# THS788_1.net
KiCad netlist of a schematic drawn in Altium Designer
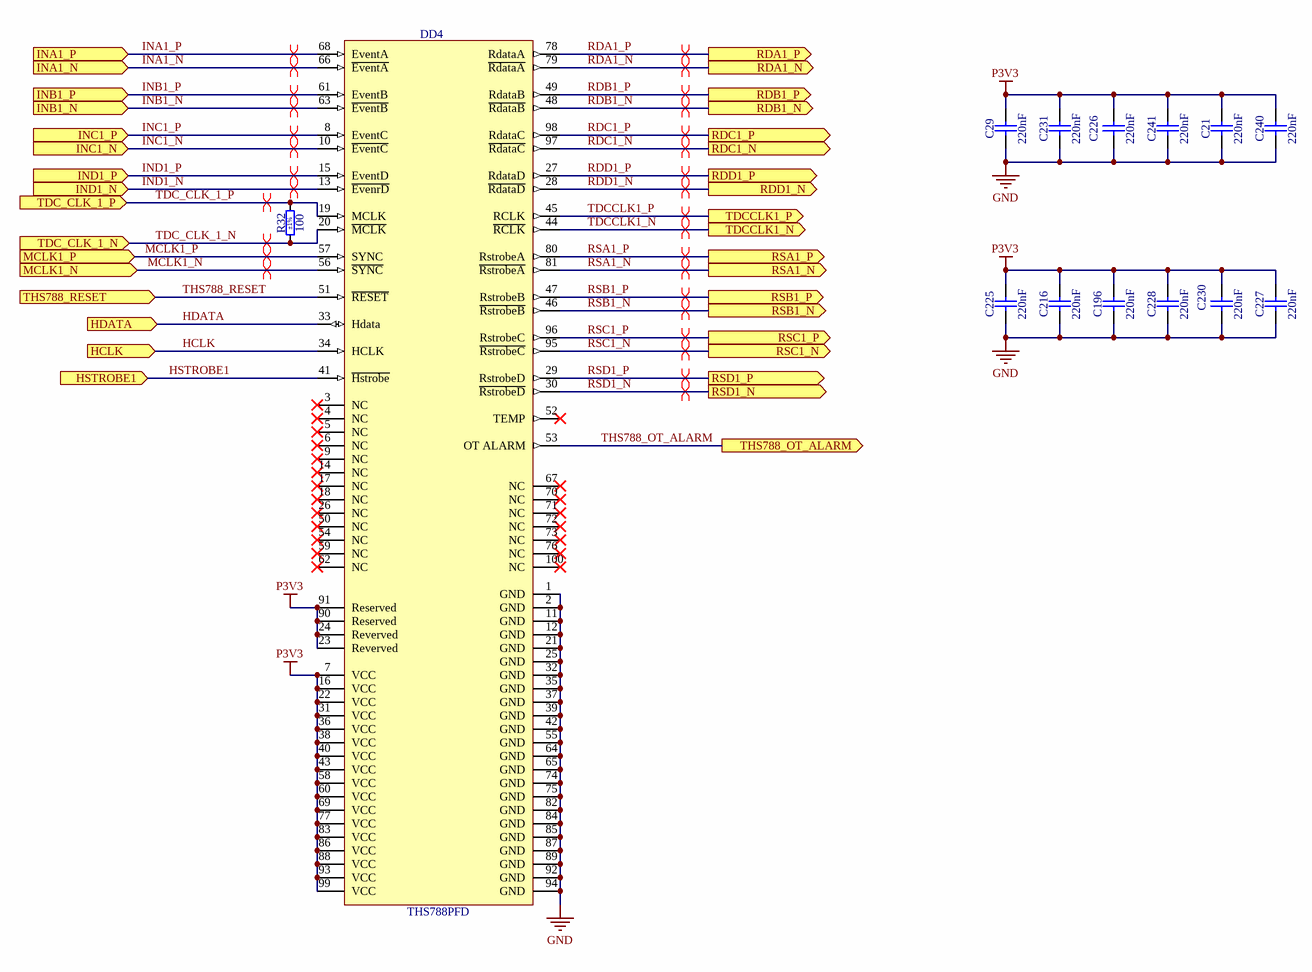
[diagram p0: THS788_1.SchDoc]

(export (version "E")
  (design (tool "Eeschema 10.0.6"))
  (components
    (comp (ref "C21")
      (value "220nF")
      (footprint "CAPC2012X135N")
      (description "Non-polarised capacitor")
      (fields
        (field (name "PART NUMBER") "CC0805_220NF_50V_10%_X7R")
        (field (name "VOLTAGE") "50V")
        (field (name "AUTHOR") "CERN DEM JLC")
      )
      (libsource (lib "Capacitors") (part "Capacitor - non polarized"))
    )
    (comp (ref "C29")
      (value "220nF")
      (footprint "CAPC2012X135N")
      (description "Non-polarised capacitor")
      (fields
        (field (name "PART NUMBER") "CC0805_220NF_50V_10%_X7R")
        (field (name "VOLTAGE") "50V")
        (field (name "AUTHOR") "CERN DEM JLC")
      )
      (libsource (lib "Capacitors") (part "Capacitor - non polarized"))
    )
    (comp (ref "C196")
      (value "220nF")
      (footprint "CAPC2012X135N")
      (description "Non-polarised capacitor")
      (fields
        (field (name "PART NUMBER") "CC0805_220NF_50V_10%_X7R")
        (field (name "VOLTAGE") "50V")
        (field (name "AUTHOR") "CERN DEM JLC")
      )
      (libsource (lib "Capacitors") (part "Capacitor - non polarized"))
    )
    (comp (ref "C216")
      (value "220nF")
      (footprint "CAPC2012X135N")
      (description "Non-polarised capacitor")
      (fields
        (field (name "PART NUMBER") "CC0805_220NF_50V_10%_X7R")
        (field (name "VOLTAGE") "50V")
        (field (name "AUTHOR") "CERN DEM JLC")
      )
      (libsource (lib "Capacitors") (part "Capacitor - non polarized"))
    )
    (comp (ref "C225")
      (value "220nF")
      (footprint "CAPC2012X135N")
      (description "Non-polarised capacitor")
      (fields
        (field (name "PART NUMBER") "CC0805_220NF_50V_10%_X7R")
        (field (name "VOLTAGE") "50V")
        (field (name "AUTHOR") "CERN DEM JLC")
      )
      (libsource (lib "Capacitors") (part "Capacitor - non polarized"))
    )
    (comp (ref "C226")
      (value "220nF")
      (footprint "CAPC2012X135N")
      (description "Non-polarised capacitor")
      (fields
        (field (name "PART NUMBER") "CC0805_220NF_50V_10%_X7R")
        (field (name "VOLTAGE") "50V")
        (field (name "AUTHOR") "CERN DEM JLC")
      )
      (libsource (lib "Capacitors") (part "Capacitor - non polarized"))
    )
    (comp (ref "C227")
      (value "220nF")
      (footprint "CAPC2012X135N")
      (description "Non-polarised capacitor")
      (fields
        (field (name "PART NUMBER") "CC0805_220NF_50V_10%_X7R")
        (field (name "VOLTAGE") "50V")
        (field (name "AUTHOR") "CERN DEM JLC")
      )
      (libsource (lib "Capacitors") (part "Capacitor - non polarized"))
    )
    (comp (ref "C228")
      (value "220nF")
      (footprint "CAPC2012X135N")
      (description "Non-polarised capacitor")
      (fields
        (field (name "PART NUMBER") "CC0805_220NF_50V_10%_X7R")
        (field (name "VOLTAGE") "50V")
        (field (name "AUTHOR") "CERN DEM JLC")
      )
      (libsource (lib "Capacitors") (part "Capacitor - non polarized"))
    )
    (comp (ref "C230")
      (value "220nF")
      (footprint "CAPC2012X135N")
      (description "Non-polarised capacitor")
      (fields
        (field (name "PART NUMBER") "CC0805_220NF_50V_10%_X7R")
        (field (name "VOLTAGE") "50V")
        (field (name "AUTHOR") "CERN DEM JLC")
      )
      (libsource (lib "Capacitors") (part "Capacitor - non polarized"))
    )
    (comp (ref "C231")
      (value "220nF")
      (footprint "CAPC2012X135N")
      (description "Non-polarised capacitor")
      (fields
        (field (name "PART NUMBER") "CC0805_220NF_50V_10%_X7R")
        (field (name "VOLTAGE") "50V")
        (field (name "AUTHOR") "CERN DEM JLC")
      )
      (libsource (lib "Capacitors") (part "Capacitor - non polarized"))
    )
    (comp (ref "C240")
      (value "220nF")
      (footprint "CAPC2012X135N")
      (description "Non-polarised capacitor")
      (fields
        (field (name "PART NUMBER") "CC0805_220NF_50V_10%_X7R")
        (field (name "VOLTAGE") "50V")
        (field (name "AUTHOR") "CERN DEM JLC")
      )
      (libsource (lib "Capacitors") (part "Capacitor - non polarized"))
    )
    (comp (ref "C241")
      (value "220nF")
      (footprint "CAPC2012X135N")
      (description "Non-polarised capacitor")
      (fields
        (field (name "PART NUMBER") "CC0805_220NF_50V_10%_X7R")
        (field (name "VOLTAGE") "50V")
        (field (name "AUTHOR") "CERN DEM JLC")
      )
      (libsource (lib "Capacitors") (part "Capacitor - non polarized"))
    )
    (comp (ref "DD4")
      (value "THS788PFD")
      (footprint "TEXAS_PFD (S-PQFP-G100)")
      (description "Quad-Channel Time Measurement Unit (TMU)")
      (fields (field (name "MANUFACTURER") "TEXAS INSTRUMENTS") (field (name "AUTHOR") "CERN DEM HF"))
      (libsource (lib "ICs And Semiconductors") (part "THS788PFD"))
    )
    (comp (ref "R32")
      (value "100")
      (footprint "RESC1608X55N")
      (description "Resistor - 1%")
      (fields
        (field (name "TOLERANCE") "±1%")
        (field (name "PART NUMBER") "R0603_100R_1%_0.1W_100PPM")
        (field (name "POWER") "0.1W")
        (field (name "AUTHOR") "CERN DEM JLC")
      )
      (libsource (lib "Resistors") (part "Resistor - 1%"))
    )
  )
  (nets
    (net (code "1") (name "/HCLK") (class "Default")
      (node (ref "DD4") (pin "34") (pinfunction "HCLK_34") (pintype "input"))
    )
    (net (code "2") (name "/HDATA") (class "Default")
      (node (ref "DD4") (pin "33") (pinfunction "Hdata_33") (pintype "bidirectional"))
    )
    (net (code "3") (name "/HSTROBE1") (class "Default")
      (node (ref "DD4") (pin "41") (pinfunction "~{Hstrobe}_41") (pintype "input"))
    )
    (net (code "4") (name "/INA1_N") (class "Default")
      (node (ref "DD4") (pin "66") (pinfunction "~{EventA}_66") (pintype "input"))
    )
    (net (code "5") (name "/INA1_P") (class "Default")
      (node (ref "DD4") (pin "68") (pinfunction "EventA_68") (pintype "input"))
    )
    (net (code "6") (name "/INB1_N") (class "Default")
      (node (ref "DD4") (pin "63") (pinfunction "~{EventB}_63") (pintype "input"))
    )
    (net (code "7") (name "/INB1_P") (class "Default")
      (node (ref "DD4") (pin "61") (pinfunction "EventB_61") (pintype "input"))
    )
    (net (code "8") (name "/INC1_N") (class "Default")
      (node (ref "DD4") (pin "10") (pinfunction "~{EventC}_10") (pintype "input"))
    )
    (net (code "9") (name "/INC1_P") (class "Default")
      (node (ref "DD4") (pin "8") (pinfunction "EventC_8") (pintype "input"))
    )
    (net (code "10") (name "/IND1_N") (class "Default")
      (node (ref "DD4") (pin "13") (pinfunction "~{EvenrD}_13") (pintype "input"))
    )
    (net (code "11") (name "/IND1_P") (class "Default")
      (node (ref "DD4") (pin "15") (pinfunction "EventD_15") (pintype "input"))
    )
    (net (code "12") (name "/MCLK1_N") (class "Default")
      (node (ref "DD4") (pin "56") (pinfunction "~{SYNC}_56") (pintype "input"))
    )
    (net (code "13") (name "/MCLK1_P") (class "Default")
      (node (ref "DD4") (pin "57") (pinfunction "SYNC_57") (pintype "input"))
    )
    (net (code "14") (name "/RDA1_N") (class "Default")
      (node (ref "DD4") (pin "79") (pinfunction "~{RdataA}_79") (pintype "output"))
    )
    (net (code "15") (name "/RDA1_P") (class "Default")
      (node (ref "DD4") (pin "78") (pinfunction "RdataA_78") (pintype "output"))
    )
    (net (code "16") (name "/RDB1_N") (class "Default")
      (node (ref "DD4") (pin "48") (pinfunction "~{RdataB}_48") (pintype "output"))
    )
    (net (code "17") (name "/RDB1_P") (class "Default")
      (node (ref "DD4") (pin "49") (pinfunction "RdataB_49") (pintype "output"))
    )
    (net (code "18") (name "/RDC1_N") (class "Default")
      (node (ref "DD4") (pin "97") (pinfunction "~{RdataC}_97") (pintype "output"))
    )
    (net (code "19") (name "/RDC1_P") (class "Default")
      (node (ref "DD4") (pin "98") (pinfunction "RdataC_98") (pintype "output"))
    )
    (net (code "20") (name "/RDD1_N") (class "Default")
      (node (ref "DD4") (pin "28") (pinfunction "~{RdataD}_28") (pintype "output"))
    )
    (net (code "21") (name "/RDD1_P") (class "Default")
      (node (ref "DD4") (pin "27") (pinfunction "RdataD_27") (pintype "output"))
    )
    (net (code "22") (name "/RSA1_N") (class "Default")
      (node (ref "DD4") (pin "81") (pinfunction "~{RstrobeA}_81") (pintype "output"))
    )
    (net (code "23") (name "/RSA1_P") (class "Default")
      (node (ref "DD4") (pin "80") (pinfunction "RstrobeA_80") (pintype "output"))
    )
    (net (code "24") (name "/RSB1_N") (class "Default")
      (node (ref "DD4") (pin "46") (pinfunction "~{RstrobeB}_46") (pintype "output"))
    )
    (net (code "25") (name "/RSB1_P") (class "Default")
      (node (ref "DD4") (pin "47") (pinfunction "RstrobeB_47") (pintype "output"))
    )
    (net (code "26") (name "/RSC1_N") (class "Default")
      (node (ref "DD4") (pin "95") (pinfunction "~{RstrobeC}_95") (pintype "output"))
    )
    (net (code "27") (name "/RSC1_P") (class "Default")
      (node (ref "DD4") (pin "96") (pinfunction "RstrobeC_96") (pintype "output"))
    )
    (net (code "28") (name "/RSD1_N") (class "Default")
      (node (ref "DD4") (pin "30") (pinfunction "~{RstrobeD}_30") (pintype "output"))
    )
    (net (code "29") (name "/RSD1_P") (class "Default")
      (node (ref "DD4") (pin "29") (pinfunction "RstrobeD_29") (pintype "output"))
    )
    (net (code "30") (name "/TDCCLK1_N") (class "Default")
      (node (ref "DD4") (pin "44") (pinfunction "~{RCLK}_44") (pintype "output"))
    )
    (net (code "31") (name "/TDCCLK1_P") (class "Default")
      (node (ref "DD4") (pin "45") (pinfunction "RCLK_45") (pintype "output"))
    )
    (net (code "32") (name "/TDC_CLK_1_N") (class "Default")
      (node (ref "DD4") (pin "20") (pinfunction "~{MCLK}_20") (pintype "input"))
      (node (ref "R32") (pin "1") (pinfunction "1_1") (pintype "passive"))
    )
    (net (code "33") (name "/TDC_CLK_1_P") (class "Default")
      (node (ref "DD4") (pin "19") (pinfunction "MCLK_19") (pintype "input"))
      (node (ref "R32") (pin "2") (pinfunction "2_2") (pintype "passive"))
    )
    (net (code "34") (name "/THS788_OT_ALARM") (class "Default")
      (node (ref "DD4") (pin "53") (pinfunction "OT_ALARM_53") (pintype "output"))
    )
    (net (code "35") (name "/THS788_RESET") (class "Default")
      (node (ref "DD4") (pin "51") (pinfunction "~{RESET}_51") (pintype "input"))
    )
    (net (code "36") (name "GND") (class "Default")
      (node (ref "C196") (pin "1") (pinfunction "1_1") (pintype "passive"))
      (node (ref "C21") (pin "1") (pinfunction "1_1") (pintype "passive"))
      (node (ref "C216") (pin "1") (pinfunction "1_1") (pintype "passive"))
      (node (ref "C225") (pin "1") (pinfunction "1_1") (pintype "passive"))
      (node (ref "C226") (pin "1") (pinfunction "1_1") (pintype "passive"))
      (node (ref "C227") (pin "1") (pinfunction "1_1") (pintype "passive"))
      (node (ref "C228") (pin "1") (pinfunction "1_1") (pintype "passive"))
      (node (ref "C230") (pin "1") (pinfunction "1_1") (pintype "passive"))
      (node (ref "C231") (pin "1") (pinfunction "1_1") (pintype "passive"))
      (node (ref "C240") (pin "1") (pinfunction "1_1") (pintype "passive"))
      (node (ref "C241") (pin "1") (pinfunction "1_1") (pintype "passive"))
      (node (ref "C29") (pin "1") (pinfunction "1_1") (pintype "passive"))
      (node (ref "DD4") (pin "1") (pinfunction "GND_1") (pintype "power_in"))
      (node (ref "DD4") (pin "11") (pinfunction "GND_11") (pintype "power_in"))
      (node (ref "DD4") (pin "12") (pinfunction "GND_12") (pintype "power_in"))
      (node (ref "DD4") (pin "2") (pinfunction "GND_2") (pintype "power_in"))
      (node (ref "DD4") (pin "21") (pinfunction "GND_21") (pintype "power_in"))
      (node (ref "DD4") (pin "25") (pinfunction "GND_25") (pintype "power_in"))
      (node (ref "DD4") (pin "32") (pinfunction "GND_32") (pintype "power_in"))
      (node (ref "DD4") (pin "35") (pinfunction "GND_35") (pintype "power_in"))
      (node (ref "DD4") (pin "37") (pinfunction "GND_37") (pintype "power_in"))
      (node (ref "DD4") (pin "39") (pinfunction "GND_39") (pintype "power_in"))
      (node (ref "DD4") (pin "42") (pinfunction "GND_42") (pintype "power_in"))
      (node (ref "DD4") (pin "55") (pinfunction "GND_55") (pintype "power_in"))
      (node (ref "DD4") (pin "64") (pinfunction "GND_64") (pintype "power_in"))
      (node (ref "DD4") (pin "65") (pinfunction "GND_65") (pintype "power_in"))
      (node (ref "DD4") (pin "74") (pinfunction "GND_74") (pintype "power_in"))
      (node (ref "DD4") (pin "75") (pinfunction "GND_75") (pintype "power_in"))
      (node (ref "DD4") (pin "82") (pinfunction "GND_82") (pintype "power_in"))
      (node (ref "DD4") (pin "84") (pinfunction "GND_84") (pintype "power_in"))
      (node (ref "DD4") (pin "85") (pinfunction "GND_85") (pintype "power_in"))
      (node (ref "DD4") (pin "87") (pinfunction "GND_87") (pintype "power_in"))
      (node (ref "DD4") (pin "89") (pinfunction "GND_89") (pintype "power_in"))
      (node (ref "DD4") (pin "92") (pinfunction "GND_92") (pintype "power_in"))
      (node (ref "DD4") (pin "94") (pinfunction "GND_94") (pintype "power_in"))
    )
    (net (code "37") (name "P3V3") (class "Default")
      (node (ref "C196") (pin "2") (pinfunction "2_2") (pintype "passive"))
      (node (ref "C21") (pin "2") (pinfunction "2_2") (pintype "passive"))
      (node (ref "C216") (pin "2") (pinfunction "2_2") (pintype "passive"))
      (node (ref "C225") (pin "2") (pinfunction "2_2") (pintype "passive"))
      (node (ref "C226") (pin "2") (pinfunction "2_2") (pintype "passive"))
      (node (ref "C227") (pin "2") (pinfunction "2_2") (pintype "passive"))
      (node (ref "C228") (pin "2") (pinfunction "2_2") (pintype "passive"))
      (node (ref "C230") (pin "2") (pinfunction "2_2") (pintype "passive"))
      (node (ref "C231") (pin "2") (pinfunction "2_2") (pintype "passive"))
      (node (ref "C240") (pin "2") (pinfunction "2_2") (pintype "passive"))
      (node (ref "C241") (pin "2") (pinfunction "2_2") (pintype "passive"))
      (node (ref "C29") (pin "2") (pinfunction "2_2") (pintype "passive"))
      (node (ref "DD4") (pin "16") (pinfunction "VCC_16") (pintype "power_in"))
      (node (ref "DD4") (pin "22") (pinfunction "VCC_22") (pintype "power_in"))
      (node (ref "DD4") (pin "23") (pinfunction "Reverved_23") (pintype "passive"))
      (node (ref "DD4") (pin "24") (pinfunction "Reverved_24") (pintype "passive"))
      (node (ref "DD4") (pin "31") (pinfunction "VCC_31") (pintype "power_in"))
      (node (ref "DD4") (pin "36") (pinfunction "VCC_36") (pintype "power_in"))
      (node (ref "DD4") (pin "38") (pinfunction "VCC_38") (pintype "power_in"))
      (node (ref "DD4") (pin "40") (pinfunction "VCC_40") (pintype "power_in"))
      (node (ref "DD4") (pin "43") (pinfunction "VCC_43") (pintype "power_in"))
      (node (ref "DD4") (pin "58") (pinfunction "VCC_58") (pintype "power_in"))
      (node (ref "DD4") (pin "60") (pinfunction "VCC_60") (pintype "power_in"))
      (node (ref "DD4") (pin "69") (pinfunction "VCC_69") (pintype "power_in"))
      (node (ref "DD4") (pin "7") (pinfunction "VCC_7") (pintype "power_in"))
      (node (ref "DD4") (pin "77") (pinfunction "VCC_77") (pintype "power_in"))
      (node (ref "DD4") (pin "83") (pinfunction "VCC_83") (pintype "power_in"))
      (node (ref "DD4") (pin "86") (pinfunction "VCC_86") (pintype "power_in"))
      (node (ref "DD4") (pin "88") (pinfunction "VCC_88") (pintype "power_in"))
      (node (ref "DD4") (pin "90") (pinfunction "Reserved_90") (pintype "passive"))
      (node (ref "DD4") (pin "91") (pinfunction "Reserved_91") (pintype "passive"))
      (node (ref "DD4") (pin "93") (pinfunction "VCC_93") (pintype "power_in"))
      (node (ref "DD4") (pin "99") (pinfunction "VCC_99") (pintype "power_in"))
    )
    (net (code "38") (name "unconnected-(DD4-NC-Pad3)") (class "Default")
      (node (ref "DD4") (pin "3") (pinfunction "NC_3") (pintype "passive+no_connect"))
    )
    (net (code "39") (name "unconnected-(DD4-NC-Pad4)") (class "Default")
      (node (ref "DD4") (pin "4") (pinfunction "NC_4") (pintype "passive+no_connect"))
    )
    (net (code "40") (name "unconnected-(DD4-NC-Pad5)") (class "Default")
      (node (ref "DD4") (pin "5") (pinfunction "NC_5") (pintype "passive+no_connect"))
    )
    (net (code "41") (name "unconnected-(DD4-NC-Pad6)") (class "Default")
      (node (ref "DD4") (pin "6") (pinfunction "NC_6") (pintype "passive+no_connect"))
    )
    (net (code "42") (name "unconnected-(DD4-NC-Pad9)") (class "Default")
      (node (ref "DD4") (pin "9") (pinfunction "NC_9") (pintype "passive+no_connect"))
    )
    (net (code "43") (name "unconnected-(DD4-NC-Pad14)") (class "Default")
      (node (ref "DD4") (pin "14") (pinfunction "NC_14") (pintype "passive+no_connect"))
    )
    (net (code "44") (name "unconnected-(DD4-NC-Pad17)") (class "Default")
      (node (ref "DD4") (pin "17") (pinfunction "NC_17") (pintype "passive+no_connect"))
    )
    (net (code "45") (name "unconnected-(DD4-NC-Pad18)") (class "Default")
      (node (ref "DD4") (pin "18") (pinfunction "NC_18") (pintype "passive+no_connect"))
    )
    (net (code "46") (name "unconnected-(DD4-NC-Pad26)") (class "Default")
      (node (ref "DD4") (pin "26") (pinfunction "NC_26") (pintype "passive+no_connect"))
    )
    (net (code "47") (name "unconnected-(DD4-NC-Pad50)") (class "Default")
      (node (ref "DD4") (pin "50") (pinfunction "NC_50") (pintype "passive+no_connect"))
    )
    (net (code "48") (name "unconnected-(DD4-NC-Pad54)") (class "Default")
      (node (ref "DD4") (pin "54") (pinfunction "NC_54") (pintype "passive+no_connect"))
    )
    (net (code "49") (name "unconnected-(DD4-NC-Pad59)") (class "Default")
      (node (ref "DD4") (pin "59") (pinfunction "NC_59") (pintype "passive+no_connect"))
    )
    (net (code "50") (name "unconnected-(DD4-NC-Pad62)") (class "Default")
      (node (ref "DD4") (pin "62") (pinfunction "NC_62") (pintype "passive+no_connect"))
    )
    (net (code "51") (name "unconnected-(DD4-NC-Pad67)") (class "Default")
      (node (ref "DD4") (pin "67") (pinfunction "NC_67") (pintype "passive+no_connect"))
    )
    (net (code "52") (name "unconnected-(DD4-NC-Pad70)") (class "Default")
      (node (ref "DD4") (pin "70") (pinfunction "NC_70") (pintype "passive+no_connect"))
    )
    (net (code "53") (name "unconnected-(DD4-NC-Pad71)") (class "Default")
      (node (ref "DD4") (pin "71") (pinfunction "NC_71") (pintype "passive+no_connect"))
    )
    (net (code "54") (name "unconnected-(DD4-NC-Pad72)") (class "Default")
      (node (ref "DD4") (pin "72") (pinfunction "NC_72") (pintype "passive+no_connect"))
    )
    (net (code "55") (name "unconnected-(DD4-NC-Pad73)") (class "Default")
      (node (ref "DD4") (pin "73") (pinfunction "NC_73") (pintype "passive+no_connect"))
    )
    (net (code "56") (name "unconnected-(DD4-NC-Pad76)") (class "Default")
      (node (ref "DD4") (pin "76") (pinfunction "NC_76") (pintype "passive+no_connect"))
    )
    (net (code "57") (name "unconnected-(DD4-NC-Pad100)") (class "Default")
      (node (ref "DD4") (pin "100") (pinfunction "NC_100") (pintype "passive+no_connect"))
    )
    (net (code "58") (name "unconnected-(DD4-TEMP-Pad52)") (class "Default")
      (node (ref "DD4") (pin "52") (pinfunction "TEMP_52") (pintype "output+no_connect"))
    )
  )
)
